# Switch.net
KiCad netlist of a schematic drawn in Altium Designer
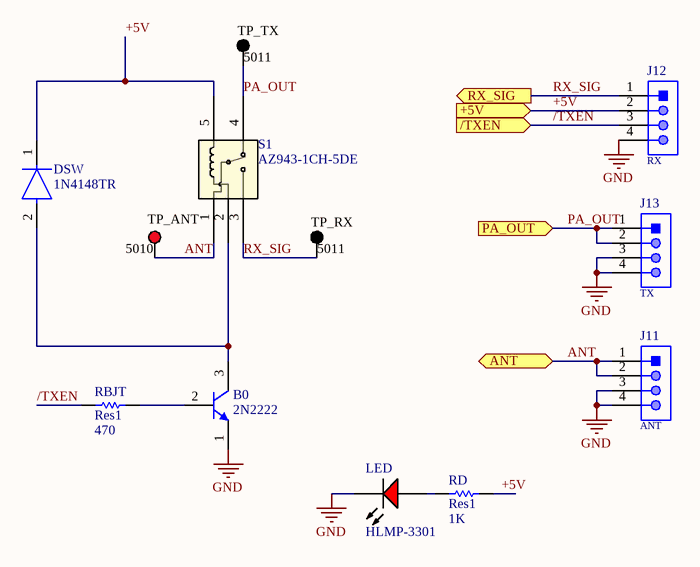
[diagram p0: Switch.SchDoc]

(export (version "E")
  (design (tool "Eeschema 10.0.6"))
  (components
    (comp (ref "B0")
      (value "2N2222")
      (footprint "MLTC-TO-18-3")
      (description "Low Power Bipolar NPN Transistor, 30 V, -65 to 200 degC, 3-Pin TO-18, RoHS, Bulk")
      (fields (field (name "MANUFACTURER") "Multicomp"))
      (libsource (lib "Altium Content Vault") (part "BJT-NPN-EBC-3"))
    )
    (comp (ref "DSW")
      (value "1N4148TR")
      (footprint "FP-6_560-5004_12-4-MFG")
      (description "DIODE GEN PURP 75V 300MA DO35")
      (libsource (lib "Altium Content Vault") (part "d7152d700b627762746794eb795d46e"))
    )
    (comp (ref "J11")
      (value "ANT")
      (footprint "61300411121")
      (description "THT Vertical Pin Header WR-PHD, Pitch 2.54 mm, Single Row, 4 pins")
      (fields
        (field (name "MANUFACTURER") "Wurth Elektronik")
        (field (name "PART NUMBER") "61300411121")
        (field (name "PUBLISHER") "WurthElektronik")
      )
      (libsource (lib "Altium Content Vault") (part "WE-CN-1P-M-R4"))
    )
    (comp (ref "J12")
      (value "RX")
      (footprint "61300411121")
      (description "THT Vertical Pin Header WR-PHD, Pitch 2.54 mm, Single Row, 4 pins")
      (fields
        (field (name "MANUFACTURER") "Wurth Elektronik")
        (field (name "PART NUMBER") "61300411121")
        (field (name "PUBLISHER") "WurthElektronik")
      )
      (libsource (lib "Altium Content Vault") (part "WE-CN-1P-M-R4"))
    )
    (comp (ref "J13")
      (value "TX")
      (footprint "61300411121")
      (description "THT Vertical Pin Header WR-PHD, Pitch 2.54 mm, Single Row, 4 pins")
      (fields
        (field (name "MANUFACTURER") "Wurth Elektronik")
        (field (name "PART NUMBER") "61300411121")
        (field (name "PUBLISHER") "WurthElektronik")
      )
      (libsource (lib "Altium Content Vault") (part "WE-CN-1P-M-R4"))
    )
    (comp (ref "LED")
      (value "HLMP-3301")
      (footprint "AVAG-HLMP-3301-2")
      (description "T-1 3/4 (5 mm) Diffused LED Lamp, 1.9 V, -40 to 100 degC, 2-Pin THD, RoHS, Bulk")
      (fields (field (name "MANUFACTURER") "Avago"))
      (libsource (lib "Altium Content Vault") (part "LED-RED-K1A2-2"))
    )
    (comp (ref "RBJT")
      (value "Res1")
      (footprint "AXIAL-0.1-RES")
      (description "Resistor")
      (fields
        (field (name "ALTIUM_VALUE") "470")
        (field (name "MANUFACTURER PART NUMBER") "CFR-25JB-52-470R")
        (field (name "TOLERANCE") "0.05")
        (field (name "PUBLISHER") "Altium Limited")
      )
      (libsource (lib "ECE295-Resistors-TH") (part "RES 470 OHM 5% 1/4W AXIAL"))
    )
    (comp (ref "RD")
      (value "Res1")
      (footprint "AXIAL-0.1-RES")
      (description "Resistor")
      (fields
        (field (name "MANUFACTURER PART NUMBER") "CFR-25JB-52-1K")
        (field (name "TOLERANCE") "0.05")
        (field (name "ALTIUM_VALUE") "1K")
        (field (name "PUBLISHER") "Altium Limited")
      )
      (libsource (lib "ECE295-Resistors-TH") (part "RES 1K OHM 5% 1/4W AXIAL"))
    )
    (comp (ref "S1")
      (value "AZ943-1CH-5DE")
      (footprint "K_AZ943-1C_AMZ")
      (description "No Description Available")
      (libsource (lib "AZ943-1CH-5DE") (part "AZ943-1CH-5DE"))
    )
    (comp (ref "TP_ANT")
      (value "5010")
      (footprint "KSTN-5010_V")
      (description "Test Point, Red, Through Hole, RoHS, Bulk")
      (fields (field (name "MANUFACTURER") "Keystone"))
      (libsource (lib "Altium Content Vault") (part "TESTPOINT_RED"))
    )
    (comp (ref "TP_RX")
      (value "5011")
      (footprint "KSTN-5011_V")
      (description "Test Point, Black, Through Hole, RoHS, Bulk")
      (fields (field (name "MANUFACTURER") "Keystone"))
      (libsource (lib "Altium Content Vault") (part "TESTPOINT_BLACK"))
    )
    (comp (ref "TP_TX")
      (value "5011")
      (footprint "KSTN-5011_V")
      (description "Test Point, Black, Through Hole, RoHS, Bulk")
      (fields (field (name "MANUFACTURER") "Keystone"))
      (libsource (lib "Altium Content Vault") (part "TESTPOINT_BLACK"))
    )
  )
  (nets
    (net (code "1") (name "/+5V") (class "Default")
      (node (ref "DSW") (pin "1") (pinfunction "C_1") (pintype "passive"))
      (node (ref "J12") (pin "2") (pinfunction "2_2") (pintype "passive"))
      (node (ref "RD") (pin "2") (pinfunction "2_2") (pintype "passive"))
      (node (ref "S1") (pin "5") (pinfunction "5_5") (pintype "passive"))
    )
    (net (code "2") (name "/ANT") (class "Default")
      (node (ref "J11") (pin "1") (pinfunction "1_1") (pintype "passive"))
      (node (ref "J11") (pin "2") (pinfunction "2_2") (pintype "passive"))
      (node (ref "S1") (pin "1") (pinfunction "1_1") (pintype "passive"))
      (node (ref "TP_ANT") (pin "1") (pinfunction "1_1") (pintype "passive"))
    )
    (net (code "3") (name "/PA_OUT") (class "Default")
      (node (ref "J13") (pin "1") (pinfunction "1_1") (pintype "passive"))
      (node (ref "J13") (pin "2") (pinfunction "2_2") (pintype "passive"))
      (node (ref "S1") (pin "4") (pinfunction "4_4") (pintype "passive"))
      (node (ref "TP_TX") (pin "1") (pinfunction "1_1") (pintype "passive"))
    )
    (net (code "4") (name "/RX_SIG") (class "Default")
      (node (ref "J12") (pin "1") (pinfunction "1_1") (pintype "passive"))
      (node (ref "S1") (pin "3") (pinfunction "3_3") (pintype "passive"))
      (node (ref "TP_RX") (pin "1") (pinfunction "1_1") (pintype "passive"))
    )
    (net (code "5") (name "/{slash}TXEN") (class "Default")
      (node (ref "J12") (pin "3") (pinfunction "3_3") (pintype "passive"))
      (node (ref "RBJT") (pin "1") (pinfunction "1_1") (pintype "passive"))
    )
    (net (code "6") (name "GND") (class "Default")
      (node (ref "B0") (pin "1") (pinfunction "E_1") (pintype "passive"))
      (node (ref "J11") (pin "3") (pinfunction "3_3") (pintype "passive"))
      (node (ref "J11") (pin "4") (pinfunction "4_4") (pintype "passive"))
      (node (ref "J12") (pin "4") (pinfunction "4_4") (pintype "passive"))
      (node (ref "J13") (pin "3") (pinfunction "3_3") (pintype "passive"))
      (node (ref "J13") (pin "4") (pinfunction "4_4") (pintype "passive"))
      (node (ref "LED") (pin "1") (pinfunction "K_1") (pintype "passive"))
    )
    (net (code "7") (name "Net-(B0-B)") (class "Default")
      (node (ref "B0") (pin "2") (pinfunction "B_2") (pintype "passive"))
      (node (ref "RBJT") (pin "2") (pinfunction "2_2") (pintype "passive"))
    )
    (net (code "8") (name "Net-(B0-C)") (class "Default")
      (node (ref "B0") (pin "3") (pinfunction "C_3") (pintype "passive"))
      (node (ref "DSW") (pin "2") (pinfunction "A_2") (pintype "passive"))
      (node (ref "S1") (pin "2") (pinfunction "2_2") (pintype "passive"))
    )
    (net (code "9") (name "Net-(LED-A)") (class "Default")
      (node (ref "LED") (pin "2") (pinfunction "A_2") (pintype "passive"))
      (node (ref "RD") (pin "1") (pinfunction "1_1") (pintype "passive"))
    )
  )
)
